# LipoCC.net
KiCad netlist of a schematic drawn in EAGLE
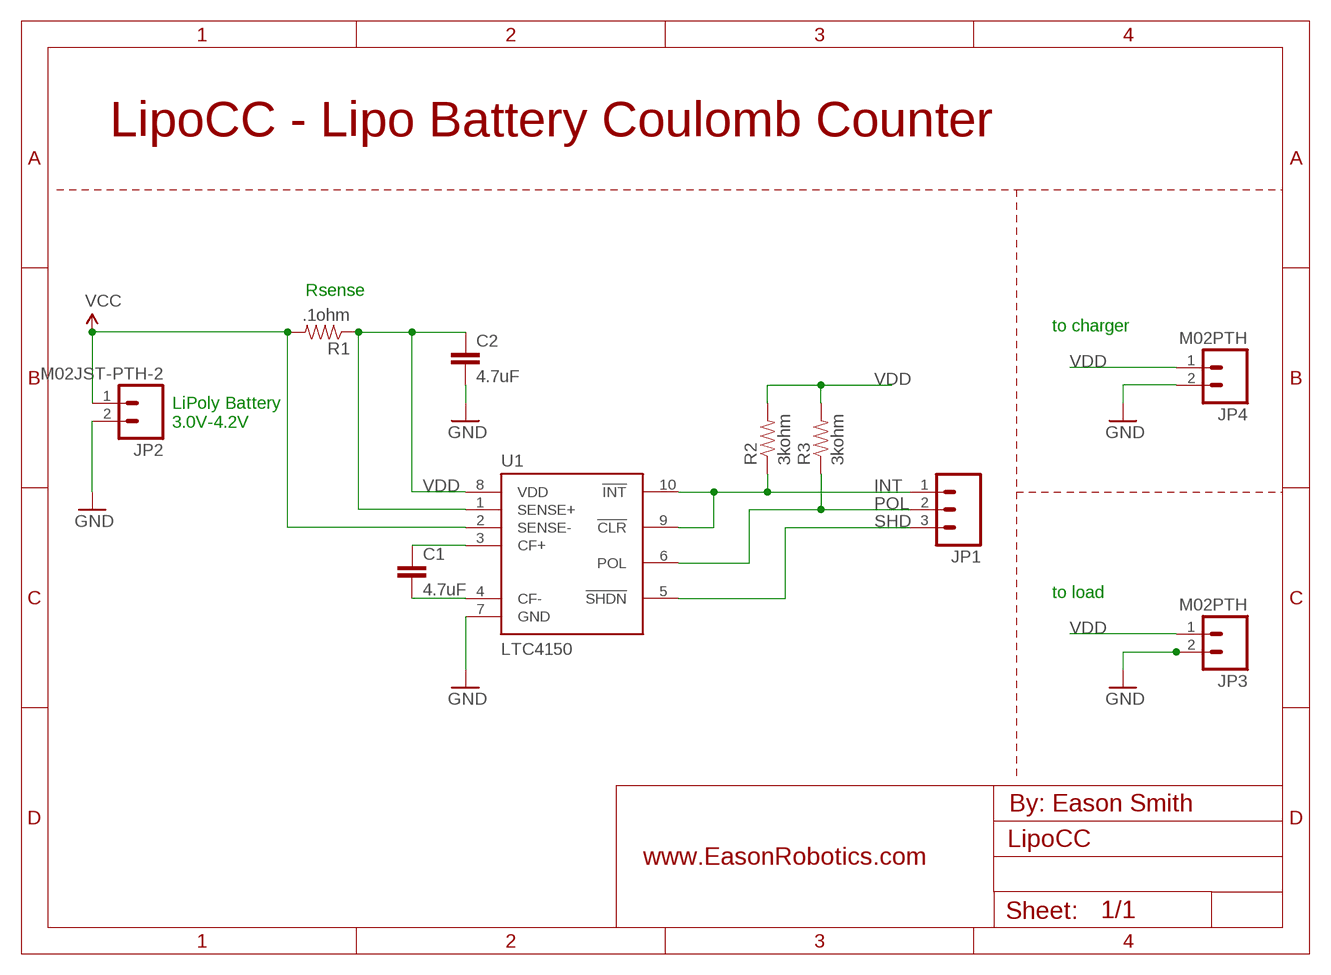
[diagram p0: schematic, sheet 1]

(export (version "E")
  (design (tool "Eeschema 10.0.6"))
  (components
    (comp (ref "C1")
      (value "4.7uF")
      (footprint "eagle-import:0603-CAP")
      (libsource (lib "eagle-import") (part "4.7UF-6.3V-10%(0603)0603"))
    )
    (comp (ref "C2")
      (value "4.7uF")
      (footprint "eagle-import:0603-CAP")
      (libsource (lib "eagle-import") (part "4.7UF-6.3V-10%(0603)0603"))
    )
    (comp (ref "JP1")
      (value "M03PTH")
      (footprint "eagle-import:1X03")
      (libsource (lib "eagle-import") (part "M03PTH"))
    )
    (comp (ref "JP2")
      (value "M02JST-PTH-2")
      (footprint "eagle-import:JST-2-PTH")
      (libsource (lib "eagle-import") (part "M02JST-PTH-2"))
    )
    (comp (ref "JP3")
      (value "M02PTH")
      (footprint "eagle-import:1X02")
      (libsource (lib "eagle-import") (part "M02PTH"))
    )
    (comp (ref "JP4")
      (value "M02PTH")
      (footprint "eagle-import:1X02")
      (libsource (lib "eagle-import") (part "M02PTH"))
    )
    (comp (ref "R1")
      (value ".1ohm")
      (footprint "eagle-import:0603-RES")
      (libsource (lib "eagle-import") (part "RESISTOR0603"))
    )
    (comp (ref "R2")
      (value "3kohm")
      (footprint "eagle-import:0603-RES")
      (libsource (lib "eagle-import") (part "3.3KOHM1/10W1%(0603)"))
    )
    (comp (ref "R3")
      (value "3kohm")
      (footprint "eagle-import:0603-RES")
      (libsource (lib "eagle-import") (part "3.3KOHM1/10W1%(0603)"))
    )
    (comp (ref "U1")
      (value "LTC4150")
      (footprint "eagle-import:MSOP10")
      (libsource (lib "eagle-import") (part "LTC4150"))
    )
  )
  (nets
    (net (code "1") (name "/INT") (class "Default")
      (node (ref "JP1") (pin "1") (pinfunction "1_1") (pintype "passive"))
      (node (ref "R2") (pin "1") (pinfunction "1_1") (pintype "passive"))
      (node (ref "U1") (pin "10") (pinfunction "~{INT}_10") (pintype "bidirectional"))
      (node (ref "U1") (pin "9") (pinfunction "~{CLR}_9") (pintype "bidirectional"))
    )
    (net (code "2") (name "/POL") (class "Default")
      (node (ref "JP1") (pin "2") (pinfunction "2_2") (pintype "passive"))
      (node (ref "R3") (pin "1") (pinfunction "1_1") (pintype "passive"))
      (node (ref "U1") (pin "6") (pinfunction "POL_6") (pintype "bidirectional"))
    )
    (net (code "3") (name "/SHD") (class "Default")
      (node (ref "JP1") (pin "3") (pinfunction "3_3") (pintype "passive"))
      (node (ref "U1") (pin "5") (pinfunction "~{SHDN}_5") (pintype "input"))
    )
    (net (code "4") (name "/VDD") (class "Default")
      (node (ref "C2") (pin "1") (pinfunction "1_1") (pintype "passive"))
      (node (ref "JP3") (pin "1") (pinfunction "1_1") (pintype "passive"))
      (node (ref "JP4") (pin "1") (pinfunction "1_1") (pintype "passive"))
      (node (ref "R1") (pin "1") (pinfunction "1_1") (pintype "passive"))
      (node (ref "R2") (pin "2") (pinfunction "2_2") (pintype "passive"))
      (node (ref "R3") (pin "2") (pinfunction "2_2") (pintype "passive"))
      (node (ref "U1") (pin "1") (pinfunction "SENSE+_1") (pintype "bidirectional"))
      (node (ref "U1") (pin "8") (pinfunction "VDD_8") (pintype "power_in"))
    )
    (net (code "5") (name "GND") (class "Default")
      (node (ref "C2") (pin "2") (pinfunction "2_2") (pintype "passive"))
      (node (ref "JP2") (pin "2") (pinfunction "2_2") (pintype "passive"))
      (node (ref "JP3") (pin "2") (pinfunction "2_2") (pintype "passive"))
      (node (ref "JP4") (pin "2") (pinfunction "2_2") (pintype "passive"))
      (node (ref "U1") (pin "7") (pinfunction "GND_7") (pintype "power_in"))
    )
    (net (code "6") (name "Net-(U1-CF+)") (class "Default")
      (node (ref "C1") (pin "1") (pinfunction "1_1") (pintype "passive"))
      (node (ref "U1") (pin "3") (pinfunction "CF+_3") (pintype "bidirectional"))
    )
    (net (code "7") (name "Net-(U1-CF-)") (class "Default")
      (node (ref "C1") (pin "2") (pinfunction "2_2") (pintype "passive"))
      (node (ref "U1") (pin "4") (pinfunction "CF-_4") (pintype "bidirectional"))
    )
    (net (code "8") (name "VCC") (class "Default")
      (node (ref "JP2") (pin "1") (pinfunction "1_1") (pintype "passive"))
      (node (ref "R1") (pin "2") (pinfunction "2_2") (pintype "passive"))
      (node (ref "U1") (pin "2") (pinfunction "SENSE-_2") (pintype "bidirectional"))
    )
  )
)
